# PCIe_MUX.net
KiCad netlist of a schematic drawn in Altium Designer
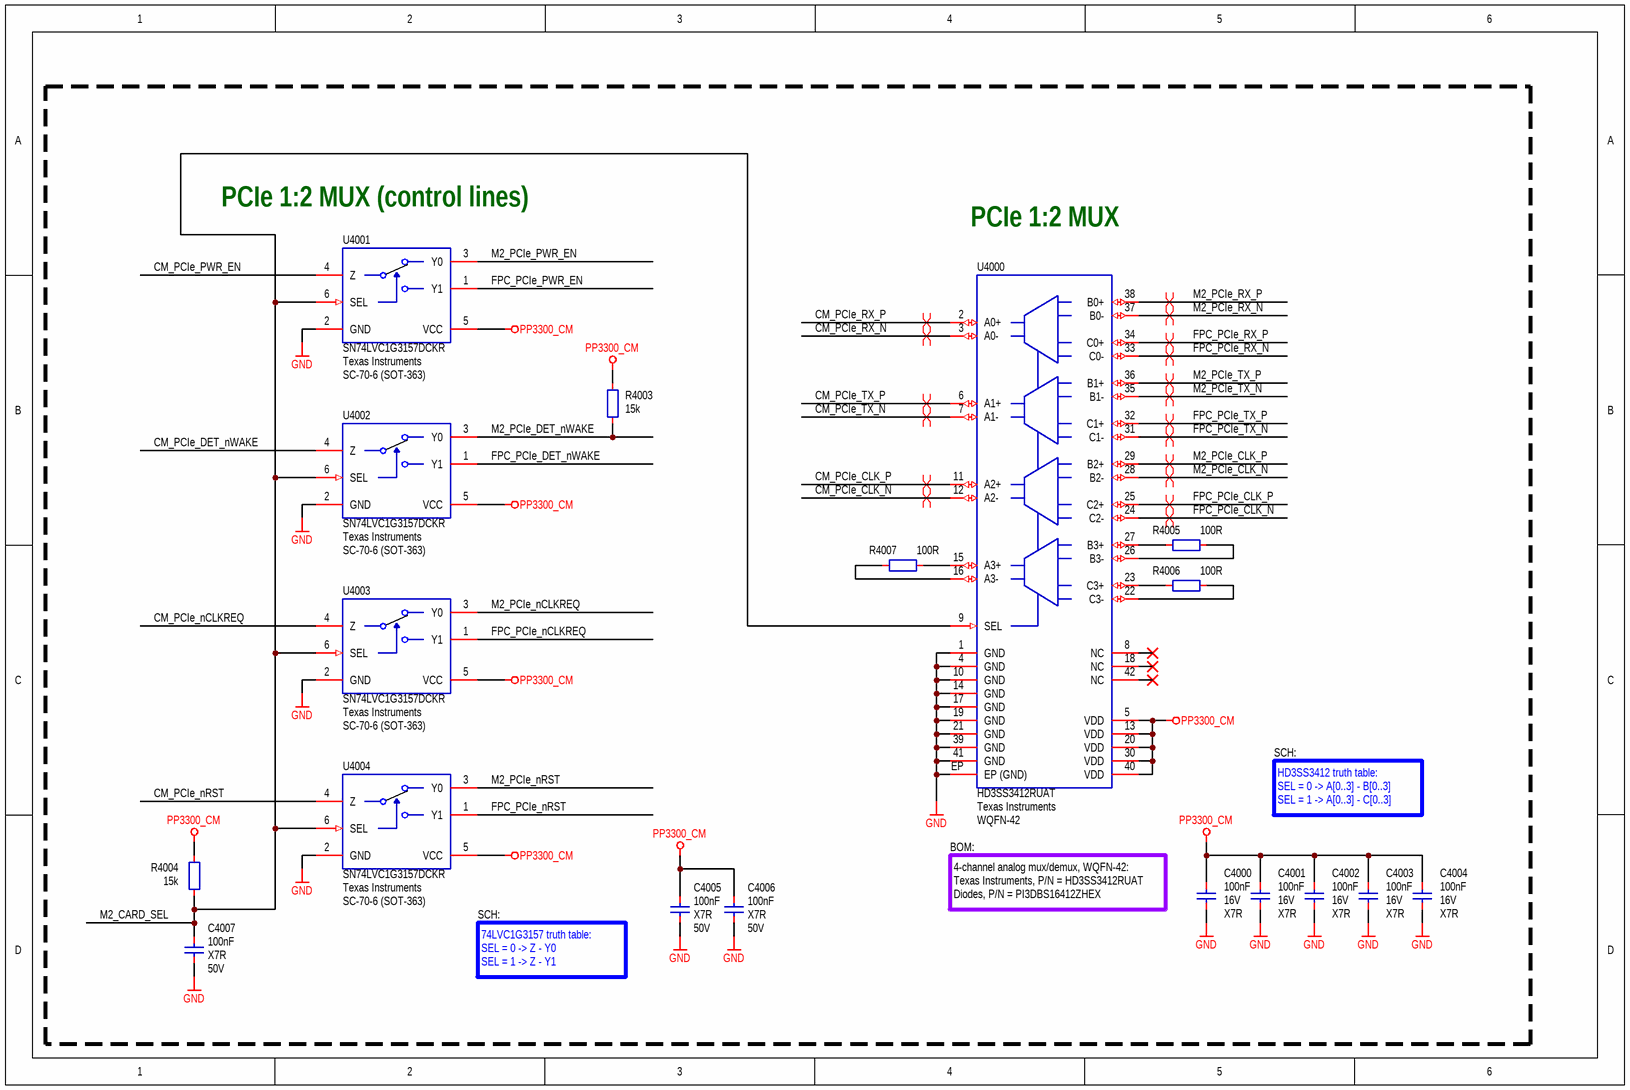
[diagram p0: PCIe_MUX.SchDoc]

(export (version "E")
  (design (tool "Eeschema 10.0.6"))
  (components
    (comp (ref "C4000")
      (value "100nF")
      (footprint "CAP_0402_R")
      (description "Capacitor; MLCC; 100nF; 16VDC; X7R; 10%; Standard; SMD; 0402 (1005);")
      (fields
        (field (name "MANUFACTURER") "Murata Manufacturing")
        (field (name "MPN") "GRM155R71C104KA88D")
        (field (name "VOLTAGE RATING") "16V")
        (field (name "DIELECTRIC") "X7R")
      )
      (libsource (lib "MirFol_db_local") (part "CAP"))
    )
    (comp (ref "C4001")
      (value "100nF")
      (footprint "CAP_0402_R")
      (description "Capacitor; MLCC; 100nF; 16VDC; X7R; 10%; Standard; SMD; 0402 (1005);")
      (fields
        (field (name "MANUFACTURER") "Murata Manufacturing")
        (field (name "MPN") "GRM155R71C104KA88D")
        (field (name "VOLTAGE RATING") "16V")
        (field (name "DIELECTRIC") "X7R")
      )
      (libsource (lib "MirFol_db_local") (part "CAP"))
    )
    (comp (ref "C4002")
      (value "100nF")
      (footprint "CAP_0402_R")
      (description "Capacitor; MLCC; 100nF; 16VDC; X7R; 10%; Standard; SMD; 0402 (1005);")
      (fields
        (field (name "MANUFACTURER") "Murata Manufacturing")
        (field (name "MPN") "GRM155R71C104KA88D")
        (field (name "VOLTAGE RATING") "16V")
        (field (name "DIELECTRIC") "X7R")
      )
      (libsource (lib "MirFol_db_local") (part "CAP"))
    )
    (comp (ref "C4003")
      (value "100nF")
      (footprint "CAP_0402_R")
      (description "Capacitor; MLCC; 100nF; 16VDC; X7R; 10%; Standard; SMD; 0402 (1005);")
      (fields
        (field (name "MANUFACTURER") "Murata Manufacturing")
        (field (name "MPN") "GRM155R71C104KA88D")
        (field (name "VOLTAGE RATING") "16V")
        (field (name "DIELECTRIC") "X7R")
      )
      (libsource (lib "MirFol_db_local") (part "CAP"))
    )
    (comp (ref "C4004")
      (value "100nF")
      (footprint "CAP_0402_R")
      (description "Capacitor; MLCC; 100nF; 16VDC; X7R; 10%; Standard; SMD; 0402 (1005);")
      (fields
        (field (name "MANUFACTURER") "Murata Manufacturing")
        (field (name "MPN") "GRM155R71C104KA88D")
        (field (name "VOLTAGE RATING") "16V")
        (field (name "DIELECTRIC") "X7R")
      )
      (libsource (lib "MirFol_db_local") (part "CAP"))
    )
    (comp (ref "C4005")
      (value "100nF")
      (footprint "CAP_0603_R")
      (description "Capacitor; MLCC; 100nF; TBD; TBD; TBD; TBD; SMD; 0603 (1608);")
      (fields
        (field (name "MANUFACTURER") "TBD")
        (field (name "VOLTAGE RATING") "50V")
        (field (name "DIELECTRIC") "X7R")
      )
      (libsource (lib "MirFol_db_local") (part "CAP"))
    )
    (comp (ref "C4006")
      (value "100nF")
      (footprint "CAP_0603_R")
      (description "Capacitor; MLCC; 100nF; TBD; TBD; TBD; TBD; SMD; 0603 (1608);")
      (fields
        (field (name "MANUFACTURER") "TBD")
        (field (name "VOLTAGE RATING") "50V")
        (field (name "DIELECTRIC") "X7R")
      )
      (libsource (lib "MirFol_db_local") (part "CAP"))
    )
    (comp (ref "C4007")
      (value "100nF")
      (footprint "CAP_0603_R")
      (description "Capacitor; MLCC; 100nF; TBD; TBD; TBD; TBD; SMD; 0603 (1608);")
      (fields
        (field (name "MANUFACTURER") "TBD")
        (field (name "VOLTAGE RATING") "50V")
        (field (name "DIELECTRIC") "X7R")
      )
      (libsource (lib "MirFol_db_local") (part "CAP"))
    )
    (comp (ref "R4003")
      (value "15k")
      (footprint "RES_0603_R")
      (description "Resistor; Thick Film; GENERIC; TBD; TBD; TBD; TBD; TBD; SMD; 0603 (1608);")
      (fields (field (name "MANUFACTURER") "Yageo Corporation") (field (name "MPN") "RC0603FR-0715KL"))
      (libsource (lib "MirFol_db_local") (part "RES"))
    )
    (comp (ref "R4004")
      (value "15k")
      (footprint "RES_0603_R")
      (description "Resistor; Thick Film; GENERIC; TBD; TBD; TBD; TBD; TBD; SMD; 0603 (1608);")
      (fields (field (name "MANUFACTURER") "Yageo Corporation") (field (name "MPN") "RC0603FR-0715KL"))
      (libsource (lib "") (part "RES_1"))
    )
    (comp (ref "R4005")
      (value "100R")
      (footprint "RES_0402_R")
      (description "Resistor; Thick Film; 1k; 1%; 62.5mW; 100PPM; 50V; Standard; SMD; 0402 (1005);")
      (fields (field (name "MANUFACTURER") "Yageo Corporation") (field (name "MPN") "RC0402FR-07100RL"))
      (libsource (lib "MirFol_db_local") (part "RES"))
    )
    (comp (ref "R4006")
      (value "100R")
      (footprint "RES_0402_R")
      (description "Resistor; Thick Film; 1k; 1%; 62.5mW; 100PPM; 50V; Standard; SMD; 0402 (1005);")
      (fields (field (name "MANUFACTURER") "Yageo Corporation") (field (name "MPN") "RC0402FR-07100RL"))
      (libsource (lib "MirFol_db_local") (part "RES"))
    )
    (comp (ref "R4007")
      (value "100R")
      (footprint "RES_0402_R")
      (description "Resistor; Thick Film; 1k; 1%; 62.5mW; 100PPM; 50V; Standard; SMD; 0402 (1005);")
      (fields (field (name "MANUFACTURER") "Yageo Corporation") (field (name "MPN") "RC0402FR-07100RL"))
      (libsource (lib "MirFol_db_local") (part "RES"))
    )
    (comp (ref "U4000")
      (value "HD3SS3412")
      (footprint "ICC_WQFN42_900X350H80_P50_EP")
      (description "ICC; Analog Mux/Demux;")
      (fields
        (field (name "MANUFACTURER") "Texas Instruments")
        (field (name "MPN") "HD3SS3412RUAT")
        (field (name "PACKAGE (CASE)") "WQFN-42")
      )
      (libsource (lib "Pineberry_Lib") (part "ICC_TXI_HD3SS3412_WQFN42"))
    )
    (comp (ref "U4001")
      (value "74LVC1G3157")
      (footprint "ICC_SOT363_SC70-6_TSSOP6_P65_R")
      (description "ICC")
      (fields
        (field (name "MANUFACTURER") "Texas Instruments")
        (field (name "MPN") "SN74LVC1G3157DCKR")
        (field (name "PACKAGE (CASE)") "SC-70-6 (SOT-363)")
      )
      (libsource (lib "MirFol_lib") (part "ICC_NXP_74LVC1G3157GW"))
    )
    (comp (ref "U4002")
      (value "74LVC1G3157")
      (footprint "ICC_SOT363_SC70-6_TSSOP6_P65_R")
      (description "ICC")
      (fields
        (field (name "MANUFACTURER") "Texas Instruments")
        (field (name "MPN") "SN74LVC1G3157DCKR")
        (field (name "PACKAGE (CASE)") "SC-70-6 (SOT-363)")
      )
      (libsource (lib "MirFol_lib") (part "ICC_NXP_74LVC1G3157GW"))
    )
    (comp (ref "U4003")
      (value "74LVC1G3157")
      (footprint "ICC_SOT363_SC70-6_TSSOP6_P65_R")
      (description "ICC")
      (fields
        (field (name "MANUFACTURER") "Texas Instruments")
        (field (name "MPN") "SN74LVC1G3157DCKR")
        (field (name "PACKAGE (CASE)") "SC-70-6 (SOT-363)")
      )
      (libsource (lib "MirFol_lib") (part "ICC_NXP_74LVC1G3157GW"))
    )
    (comp (ref "U4004")
      (value "74LVC1G3157")
      (footprint "ICC_SOT363_SC70-6_TSSOP6_P65_R")
      (description "ICC")
      (fields
        (field (name "MANUFACTURER") "Texas Instruments")
        (field (name "MPN") "SN74LVC1G3157DCKR")
        (field (name "PACKAGE (CASE)") "SC-70-6 (SOT-363)")
      )
      (libsource (lib "MirFol_lib") (part "ICC_NXP_74LVC1G3157GW"))
    )
  )
  (nets
    (net (code "1") (name "/CM_PCIe_CLK_N") (class "Default")
      (node (ref "U4000") (pin "12") (pinfunction "A2-_12") (pintype "bidirectional"))
    )
    (net (code "2") (name "/CM_PCIe_CLK_P") (class "Default")
      (node (ref "U4000") (pin "11") (pinfunction "A2+_11") (pintype "bidirectional"))
    )
    (net (code "3") (name "/CM_PCIe_DET_nWAKE") (class "Default")
      (node (ref "U4002") (pin "4") (pinfunction "Z_4") (pintype "passive"))
    )
    (net (code "4") (name "/CM_PCIe_PWR_EN") (class "Default")
      (node (ref "U4001") (pin "4") (pinfunction "Z_4") (pintype "passive"))
    )
    (net (code "5") (name "/CM_PCIe_RX_N") (class "Default")
      (node (ref "U4000") (pin "3") (pinfunction "A0-_3") (pintype "bidirectional"))
    )
    (net (code "6") (name "/CM_PCIe_RX_P") (class "Default")
      (node (ref "U4000") (pin "2") (pinfunction "A0+_2") (pintype "bidirectional"))
    )
    (net (code "7") (name "/CM_PCIe_TX_N") (class "Default")
      (node (ref "U4000") (pin "7") (pinfunction "A1-_7") (pintype "bidirectional"))
    )
    (net (code "8") (name "/CM_PCIe_TX_P") (class "Default")
      (node (ref "U4000") (pin "6") (pinfunction "A1+_6") (pintype "bidirectional"))
    )
    (net (code "9") (name "/CM_PCIe_nCLKREQ") (class "Default")
      (node (ref "U4003") (pin "4") (pinfunction "Z_4") (pintype "passive"))
    )
    (net (code "10") (name "/CM_PCIe_nRST") (class "Default")
      (node (ref "U4004") (pin "4") (pinfunction "Z_4") (pintype "passive"))
    )
    (net (code "11") (name "/FPC_PCIe_CLK_N") (class "Default")
      (node (ref "U4000") (pin "24") (pinfunction "C2-_24") (pintype "bidirectional"))
    )
    (net (code "12") (name "/FPC_PCIe_CLK_P") (class "Default")
      (node (ref "U4000") (pin "25") (pinfunction "C2+_25") (pintype "bidirectional"))
    )
    (net (code "13") (name "/FPC_PCIe_DET_nWAKE") (class "Default")
      (node (ref "U4002") (pin "1") (pinfunction "Y1_1") (pintype "passive"))
    )
    (net (code "14") (name "/FPC_PCIe_PWR_EN") (class "Default")
      (node (ref "U4001") (pin "1") (pinfunction "Y1_1") (pintype "passive"))
    )
    (net (code "15") (name "/FPC_PCIe_RX_N") (class "Default")
      (node (ref "U4000") (pin "33") (pinfunction "C0-_33") (pintype "bidirectional"))
    )
    (net (code "16") (name "/FPC_PCIe_RX_P") (class "Default")
      (node (ref "U4000") (pin "34") (pinfunction "C0+_34") (pintype "bidirectional"))
    )
    (net (code "17") (name "/FPC_PCIe_TX_N") (class "Default")
      (node (ref "U4000") (pin "31") (pinfunction "C1-_31") (pintype "bidirectional"))
    )
    (net (code "18") (name "/FPC_PCIe_TX_P") (class "Default")
      (node (ref "U4000") (pin "32") (pinfunction "C1+_32") (pintype "bidirectional"))
    )
    (net (code "19") (name "/FPC_PCIe_nCLKREQ") (class "Default")
      (node (ref "U4003") (pin "1") (pinfunction "Y1_1") (pintype "passive"))
    )
    (net (code "20") (name "/FPC_PCIe_nRST") (class "Default")
      (node (ref "U4004") (pin "1") (pinfunction "Y1_1") (pintype "passive"))
    )
    (net (code "21") (name "/M2_CARD_SEL") (class "Default")
      (node (ref "C4007") (pin "2") (pintype "passive"))
      (node (ref "R4004") (pin "2") (pinfunction "2_2") (pintype "passive"))
      (node (ref "U4000") (pin "9") (pinfunction "SEL_9") (pintype "input"))
      (node (ref "U4001") (pin "6") (pinfunction "SEL_6") (pintype "input"))
      (node (ref "U4002") (pin "6") (pinfunction "SEL_6") (pintype "input"))
      (node (ref "U4003") (pin "6") (pinfunction "SEL_6") (pintype "input"))
      (node (ref "U4004") (pin "6") (pinfunction "SEL_6") (pintype "input"))
    )
    (net (code "22") (name "/M2_PCIe_CLK_N") (class "Default")
      (node (ref "U4000") (pin "28") (pinfunction "B2-_28") (pintype "bidirectional"))
    )
    (net (code "23") (name "/M2_PCIe_CLK_P") (class "Default")
      (node (ref "U4000") (pin "29") (pinfunction "B2+_29") (pintype "bidirectional"))
    )
    (net (code "24") (name "/M2_PCIe_DET_nWAKE") (class "Default")
      (node (ref "R4003") (pin "2") (pinfunction "2_2") (pintype "passive"))
      (node (ref "U4002") (pin "3") (pinfunction "Y0_3") (pintype "passive"))
    )
    (net (code "25") (name "/M2_PCIe_PWR_EN") (class "Default")
      (node (ref "U4001") (pin "3") (pinfunction "Y0_3") (pintype "passive"))
    )
    (net (code "26") (name "/M2_PCIe_RX_N") (class "Default")
      (node (ref "U4000") (pin "37") (pinfunction "B0-_37") (pintype "bidirectional"))
    )
    (net (code "27") (name "/M2_PCIe_RX_P") (class "Default")
      (node (ref "U4000") (pin "38") (pinfunction "B0+_38") (pintype "bidirectional"))
    )
    (net (code "28") (name "/M2_PCIe_TX_N") (class "Default")
      (node (ref "U4000") (pin "35") (pinfunction "B1-_35") (pintype "bidirectional"))
    )
    (net (code "29") (name "/M2_PCIe_TX_P") (class "Default")
      (node (ref "U4000") (pin "36") (pinfunction "B1+_36") (pintype "bidirectional"))
    )
    (net (code "30") (name "/M2_PCIe_nCLKREQ") (class "Default")
      (node (ref "U4003") (pin "3") (pinfunction "Y0_3") (pintype "passive"))
    )
    (net (code "31") (name "/M2_PCIe_nRST") (class "Default")
      (node (ref "U4004") (pin "3") (pinfunction "Y0_3") (pintype "passive"))
    )
    (net (code "32") (name "GND") (class "Default")
      (node (ref "C4000") (pin "1") (pintype "passive"))
      (node (ref "C4001") (pin "1") (pintype "passive"))
      (node (ref "C4002") (pin "1") (pintype "passive"))
      (node (ref "C4003") (pin "1") (pintype "passive"))
      (node (ref "C4004") (pin "1") (pintype "passive"))
      (node (ref "C4005") (pin "1") (pintype "passive"))
      (node (ref "C4006") (pin "1") (pintype "passive"))
      (node (ref "C4007") (pin "1") (pintype "passive"))
      (node (ref "U4000") (pin "1") (pinfunction "GND_1") (pintype "power_in"))
      (node (ref "U4000") (pin "10") (pinfunction "GND_10") (pintype "power_in"))
      (node (ref "U4000") (pin "14") (pinfunction "GND_14") (pintype "power_in"))
      (node (ref "U4000") (pin "17") (pinfunction "GND_17") (pintype "power_in"))
      (node (ref "U4000") (pin "19") (pinfunction "GND_19") (pintype "power_in"))
      (node (ref "U4000") (pin "21") (pinfunction "GND_21") (pintype "power_in"))
      (node (ref "U4000") (pin "39") (pinfunction "GND_39") (pintype "power_in"))
      (node (ref "U4000") (pin "4") (pinfunction "GND_4") (pintype "power_in"))
      (node (ref "U4000") (pin "41") (pinfunction "GND_41") (pintype "power_in"))
      (node (ref "U4000") (pin "EP") (pinfunction "EP_(GND)_EP") (pintype "power_in"))
      (node (ref "U4001") (pin "2") (pinfunction "GND_2") (pintype "power_in"))
      (node (ref "U4002") (pin "2") (pinfunction "GND_2") (pintype "power_in"))
      (node (ref "U4003") (pin "2") (pinfunction "GND_2") (pintype "power_in"))
      (node (ref "U4004") (pin "2") (pinfunction "GND_2") (pintype "power_in"))
    )
    (net (code "33") (name "Net-(U4000-A3+)") (class "Default")
      (node (ref "R4007") (pin "1") (pinfunction "1_1") (pintype "passive"))
      (node (ref "U4000") (pin "15") (pinfunction "A3+_15") (pintype "bidirectional"))
    )
    (net (code "34") (name "Net-(U4000-A3-)") (class "Default")
      (node (ref "R4007") (pin "2") (pinfunction "2_2") (pintype "passive"))
      (node (ref "U4000") (pin "16") (pinfunction "A3-_16") (pintype "bidirectional"))
    )
    (net (code "35") (name "Net-(U4000-B3+)") (class "Default")
      (node (ref "R4005") (pin "2") (pinfunction "2_2") (pintype "passive"))
      (node (ref "U4000") (pin "27") (pinfunction "B3+_27") (pintype "bidirectional"))
    )
    (net (code "36") (name "Net-(U4000-B3-)") (class "Default")
      (node (ref "R4005") (pin "1") (pinfunction "1_1") (pintype "passive"))
      (node (ref "U4000") (pin "26") (pinfunction "B3-_26") (pintype "bidirectional"))
    )
    (net (code "37") (name "Net-(U4000-C3+)") (class "Default")
      (node (ref "R4006") (pin "2") (pinfunction "2_2") (pintype "passive"))
      (node (ref "U4000") (pin "23") (pinfunction "C3+_23") (pintype "bidirectional"))
    )
    (net (code "38") (name "Net-(U4000-C3-)") (class "Default")
      (node (ref "R4006") (pin "1") (pinfunction "1_1") (pintype "passive"))
      (node (ref "U4000") (pin "22") (pinfunction "C3-_22") (pintype "bidirectional"))
    )
    (net (code "39") (name "PP3300_CM") (class "Default")
      (node (ref "C4000") (pin "2") (pintype "passive"))
      (node (ref "C4001") (pin "2") (pintype "passive"))
      (node (ref "C4002") (pin "2") (pintype "passive"))
      (node (ref "C4003") (pin "2") (pintype "passive"))
      (node (ref "C4004") (pin "2") (pintype "passive"))
      (node (ref "C4005") (pin "2") (pintype "passive"))
      (node (ref "C4006") (pin "2") (pintype "passive"))
      (node (ref "R4003") (pin "1") (pinfunction "1_1") (pintype "passive"))
      (node (ref "R4004") (pin "1") (pinfunction "1_1") (pintype "passive"))
      (node (ref "U4000") (pin "13") (pinfunction "VDD_13") (pintype "power_in"))
      (node (ref "U4000") (pin "20") (pinfunction "VDD_20") (pintype "power_in"))
      (node (ref "U4000") (pin "30") (pinfunction "VDD_30") (pintype "power_in"))
      (node (ref "U4000") (pin "40") (pinfunction "VDD_40") (pintype "power_in"))
      (node (ref "U4000") (pin "5") (pinfunction "VDD_5") (pintype "power_in"))
      (node (ref "U4001") (pin "5") (pinfunction "VCC_5") (pintype "power_in"))
      (node (ref "U4002") (pin "5") (pinfunction "VCC_5") (pintype "power_in"))
      (node (ref "U4003") (pin "5") (pinfunction "VCC_5") (pintype "power_in"))
      (node (ref "U4004") (pin "5") (pinfunction "VCC_5") (pintype "power_in"))
    )
    (net (code "40") (name "unconnected-(U4000-NC-Pad8)") (class "Default")
      (node (ref "U4000") (pin "8") (pinfunction "NC_8") (pintype "passive+no_connect"))
    )
    (net (code "41") (name "unconnected-(U4000-NC-Pad18)") (class "Default")
      (node (ref "U4000") (pin "18") (pinfunction "NC_18") (pintype "passive+no_connect"))
    )
    (net (code "42") (name "unconnected-(U4000-NC-Pad42)") (class "Default")
      (node (ref "U4000") (pin "42") (pinfunction "NC_42") (pintype "passive+no_connect"))
    )
  )
)
